# 1switch.net
KiCad netlist of a schematic drawn in EAGLE
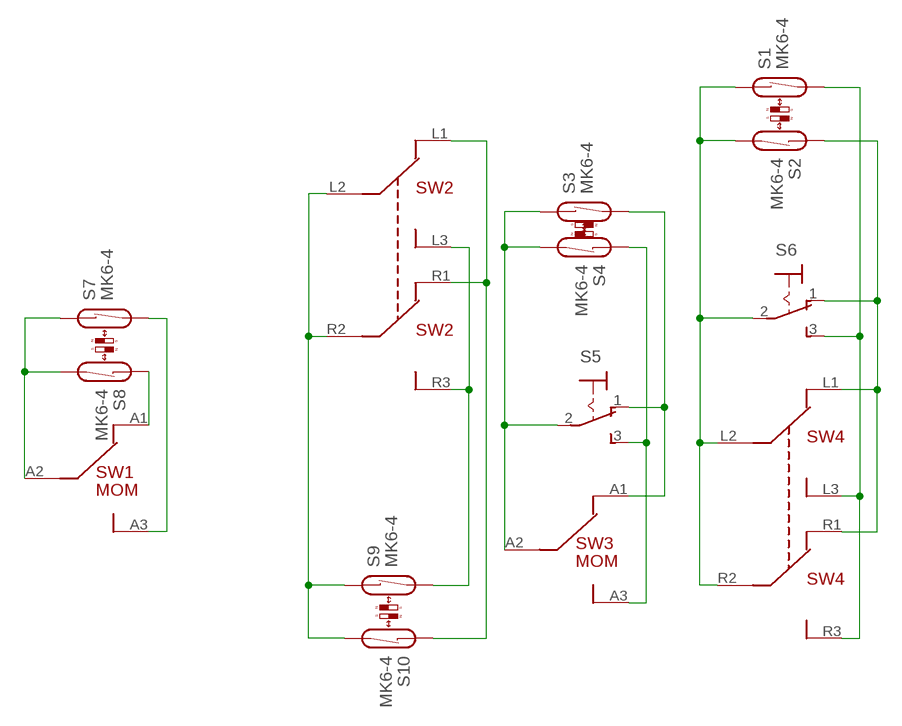
[diagram p0: schematic, sheet 1]

(export (version "E")
  (design (tool "Eeschema 10.0.6"))
  (components
    (comp (ref "S1")
      (value "MK6-4")
      (footprint "eagle-import:MK6-4")
      (libsource (lib "eagle-import") (part "REED-SWITCH-MK6-4"))
    )
    (comp (ref "S2")
      (value "MK6-4")
      (footprint "eagle-import:MK6-4")
      (libsource (lib "eagle-import") (part "REED-SWITCH-MK6-4"))
    )
    (comp (ref "S3")
      (value "MK6-4")
      (footprint "eagle-import:MK6-4")
      (libsource (lib "eagle-import") (part "REED-SWITCH-MK6-4"))
    )
    (comp (ref "S4")
      (value "MK6-4")
      (footprint "eagle-import:MK6-4")
      (libsource (lib "eagle-import") (part "REED-SWITCH-MK6-4"))
    )
    (comp (ref "S5")
      (value "M9040P7101V2")
      (footprint "eagle-import:7101MD9V21")
      (libsource (lib "eagle-import") (part "M9040P7101V2"))
    )
    (comp (ref "S6")
      (value "M9040P7101V2")
      (footprint "eagle-import:7101MD9V21")
      (libsource (lib "eagle-import") (part "M9040P7101V2"))
    )
    (comp (ref "S7")
      (value "MK6-4")
      (footprint "eagle-import:MK6-4")
      (libsource (lib "eagle-import") (part "REED-SWITCH-MK6-4"))
    )
    (comp (ref "S8")
      (value "MK6-4")
      (footprint "eagle-import:MK6-4")
      (libsource (lib "eagle-import") (part "REED-SWITCH-MK6-4"))
    )
    (comp (ref "S9")
      (value "MK6-4")
      (footprint "eagle-import:MK6-4")
      (libsource (lib "eagle-import") (part "REED-SWITCH-MK6-4"))
    )
    (comp (ref "S10")
      (value "MK6-4")
      (footprint "eagle-import:MK6-4")
      (libsource (lib "eagle-import") (part "REED-SWITCH-MK6-4"))
    )
    (comp (ref "SW1")
      (value "SPDT8I")
      (footprint "eagle-import:SPDT8I")
      (libsource (lib "eagle-import") (part "SPDT8I"))
    )
    (comp (ref "SW2")
      (value "DPDT8I")
      (footprint "eagle-import:DPDT8I")
      (libsource (lib "eagle-import") (part "DPDT8I"))
    )
    (comp (ref "SW3")
      (value "SPDT8I")
      (footprint "eagle-import:SPDT8I")
      (libsource (lib "eagle-import") (part "SPDT8I"))
    )
    (comp (ref "SW4")
      (value "DPDT8I")
      (footprint "eagle-import:DPDT8I")
      (libsource (lib "eagle-import") (part "DPDT8I"))
    )
  )
  (nets
    (net (code "1") (name "Net-(S5-O)") (class "Default")
      (node (ref "S3") (pin "2") (pinfunction "2_2") (pintype "passive"))
      (node (ref "S5") (pin "1") (pinfunction "O_1") (pintype "passive"))
      (node (ref "SW3") (pin "A1") (pinfunction "A1_A1") (pintype "bidirectional"))
    )
    (net (code "2") (name "Net-(S5-P)") (class "Default")
      (node (ref "S3") (pin "1") (pinfunction "1_1") (pintype "passive"))
      (node (ref "S4") (pin "2") (pinfunction "2_2") (pintype "passive"))
      (node (ref "S5") (pin "2") (pinfunction "P_2") (pintype "passive"))
      (node (ref "SW3") (pin "A2") (pinfunction "A2_A2") (pintype "bidirectional"))
    )
    (net (code "3") (name "Net-(S5-S)") (class "Default")
      (node (ref "S4") (pin "1") (pinfunction "1_1") (pintype "passive"))
      (node (ref "S5") (pin "3") (pinfunction "S_3") (pintype "passive"))
      (node (ref "SW3") (pin "A3") (pinfunction "A3_A3") (pintype "bidirectional"))
    )
    (net (code "4") (name "Net-(S6-O)") (class "Default")
      (node (ref "S2") (pin "1") (pinfunction "1_1") (pintype "passive"))
      (node (ref "S6") (pin "1") (pinfunction "O_1") (pintype "passive"))
      (node (ref "SW4") (pin "L1") (pinfunction "A1_L1") (pintype "bidirectional"))
      (node (ref "SW4") (pin "R1") (pinfunction "B1_R1") (pintype "bidirectional"))
    )
    (net (code "5") (name "Net-(S6-P)") (class "Default")
      (node (ref "S1") (pin "1") (pinfunction "1_1") (pintype "passive"))
      (node (ref "S2") (pin "2") (pinfunction "2_2") (pintype "passive"))
      (node (ref "S6") (pin "2") (pinfunction "P_2") (pintype "passive"))
      (node (ref "SW4") (pin "L2") (pinfunction "A2_L2") (pintype "bidirectional"))
      (node (ref "SW4") (pin "R2") (pinfunction "B2_R2") (pintype "bidirectional"))
    )
    (net (code "6") (name "Net-(S6-S)") (class "Default")
      (node (ref "S1") (pin "2") (pinfunction "2_2") (pintype "passive"))
      (node (ref "S6") (pin "3") (pinfunction "S_3") (pintype "passive"))
      (node (ref "SW4") (pin "L3") (pinfunction "A3_L3") (pintype "bidirectional"))
      (node (ref "SW4") (pin "R3") (pinfunction "B3_R3") (pintype "bidirectional"))
    )
    (net (code "7") (name "Net-(S7-Pad1)") (class "Default")
      (node (ref "S7") (pin "1") (pinfunction "1_1") (pintype "passive"))
      (node (ref "S8") (pin "2") (pinfunction "2_2") (pintype "passive"))
      (node (ref "SW1") (pin "A2") (pinfunction "A2_A2") (pintype "bidirectional"))
    )
    (net (code "8") (name "Net-(S7-Pad2)") (class "Default")
      (node (ref "S7") (pin "2") (pinfunction "2_2") (pintype "passive"))
      (node (ref "SW1") (pin "A3") (pinfunction "A3_A3") (pintype "bidirectional"))
    )
    (net (code "9") (name "Net-(S8-Pad1)") (class "Default")
      (node (ref "S8") (pin "1") (pinfunction "1_1") (pintype "passive"))
      (node (ref "SW1") (pin "A1") (pinfunction "A1_A1") (pintype "bidirectional"))
    )
    (net (code "10") (name "Net-(SW2-A1)") (class "Default")
      (node (ref "S10") (pin "1") (pinfunction "1_1") (pintype "passive"))
      (node (ref "SW2") (pin "L1") (pinfunction "A1_L1") (pintype "bidirectional"))
      (node (ref "SW2") (pin "R1") (pinfunction "B1_R1") (pintype "bidirectional"))
    )
    (net (code "11") (name "Net-(SW2-A2)") (class "Default")
      (node (ref "S10") (pin "2") (pinfunction "2_2") (pintype "passive"))
      (node (ref "S9") (pin "1") (pinfunction "1_1") (pintype "passive"))
      (node (ref "SW2") (pin "L2") (pinfunction "A2_L2") (pintype "bidirectional"))
      (node (ref "SW2") (pin "R2") (pinfunction "B2_R2") (pintype "bidirectional"))
    )
    (net (code "12") (name "Net-(SW2-A3)") (class "Default")
      (node (ref "S9") (pin "2") (pinfunction "2_2") (pintype "passive"))
      (node (ref "SW2") (pin "L3") (pinfunction "A3_L3") (pintype "bidirectional"))
      (node (ref "SW2") (pin "R3") (pinfunction "B3_R3") (pintype "bidirectional"))
    )
  )
)
